# bristol_longshot.net
KiCad netlist of a schematic drawn in EAGLE
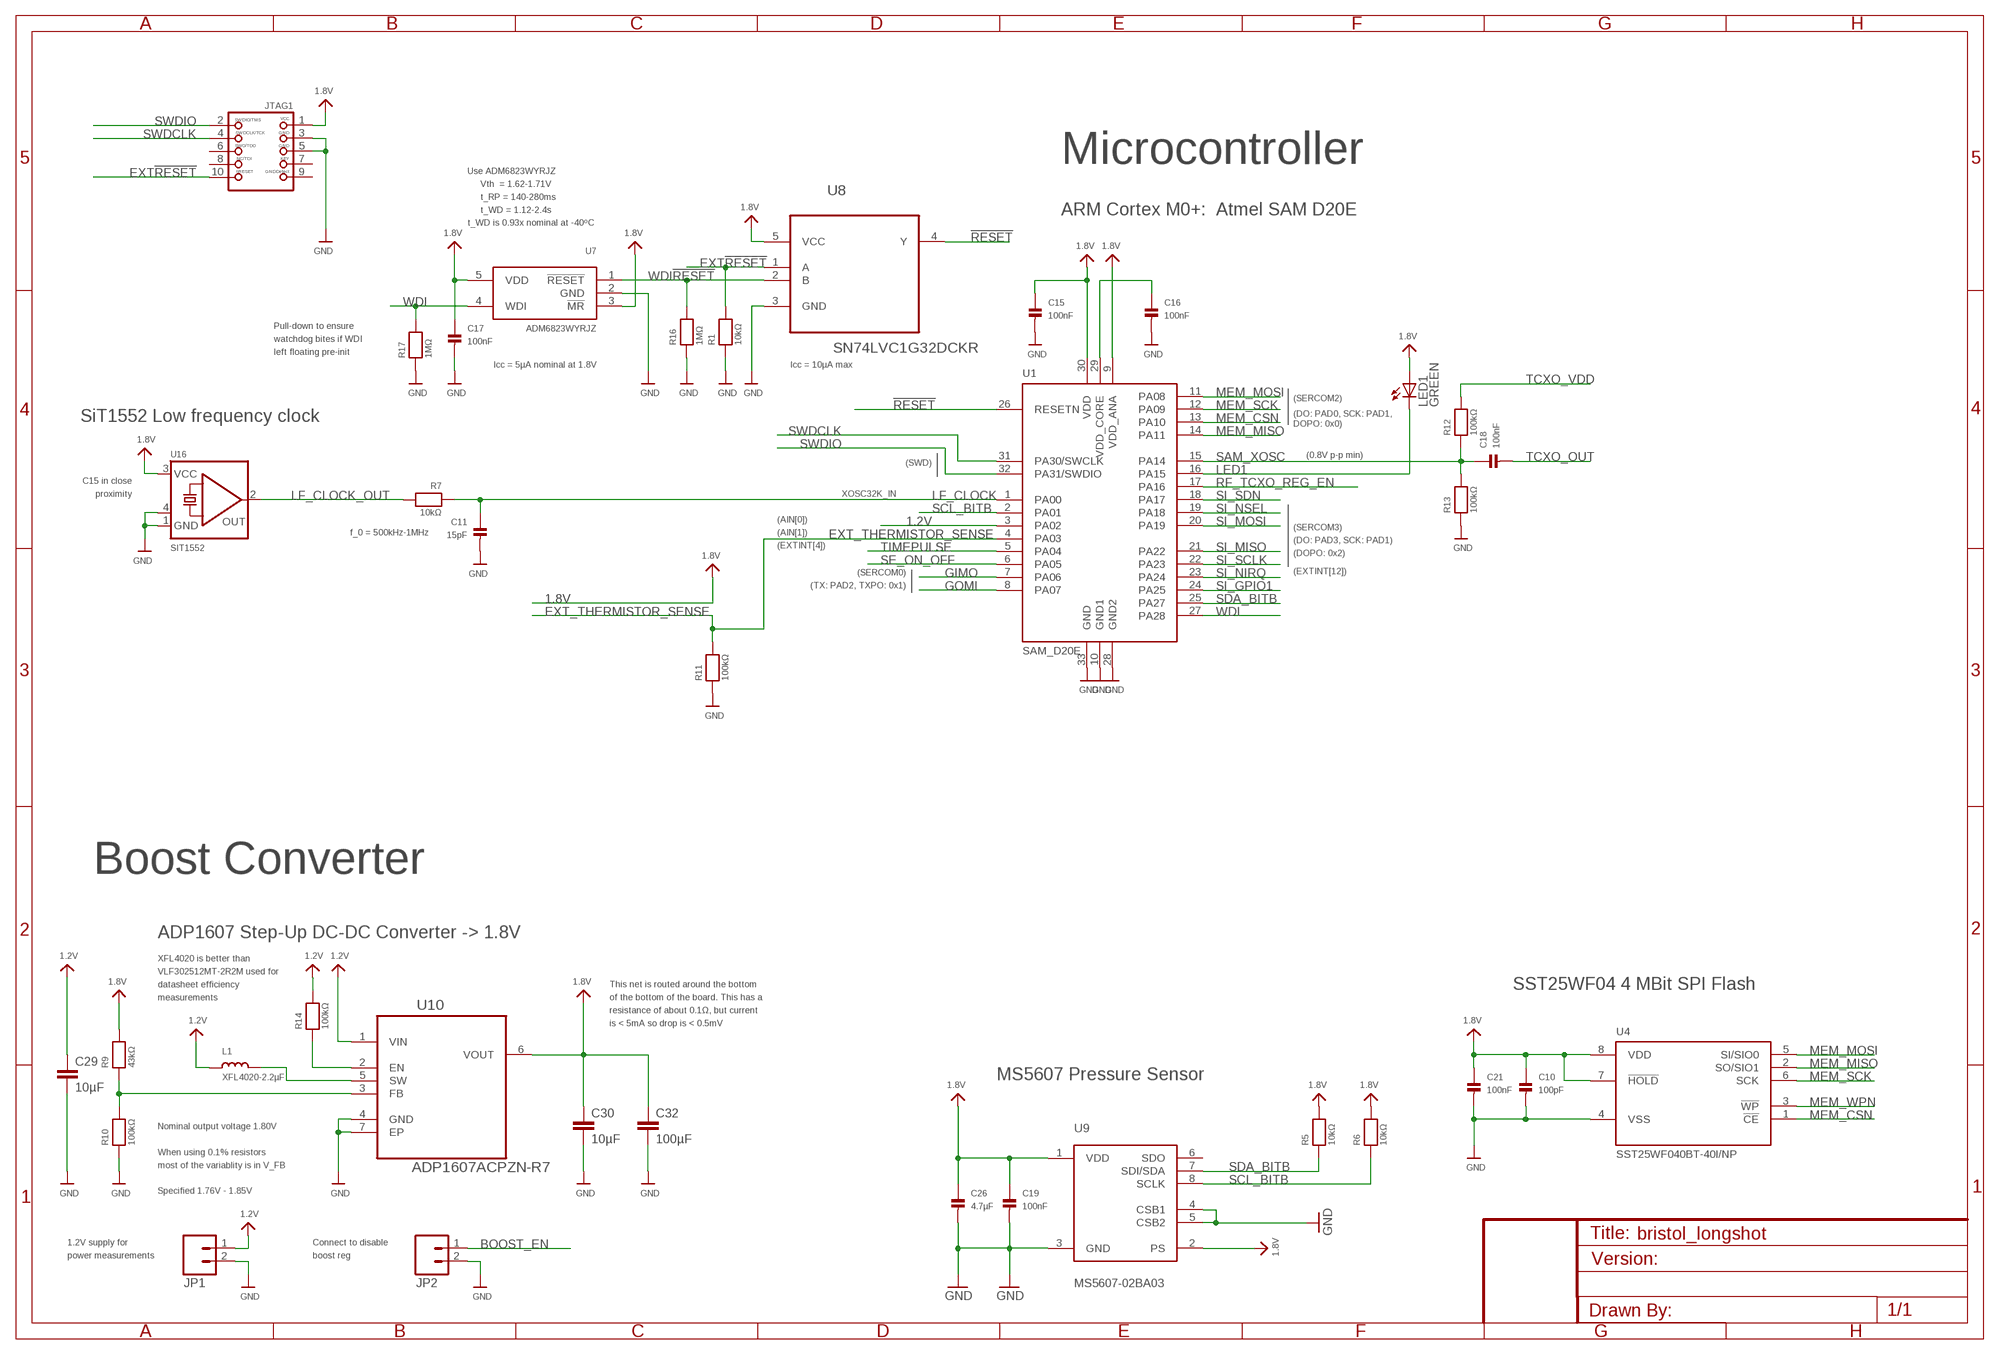
[diagram p0: schematic, sheet 1, part 1 of 2]
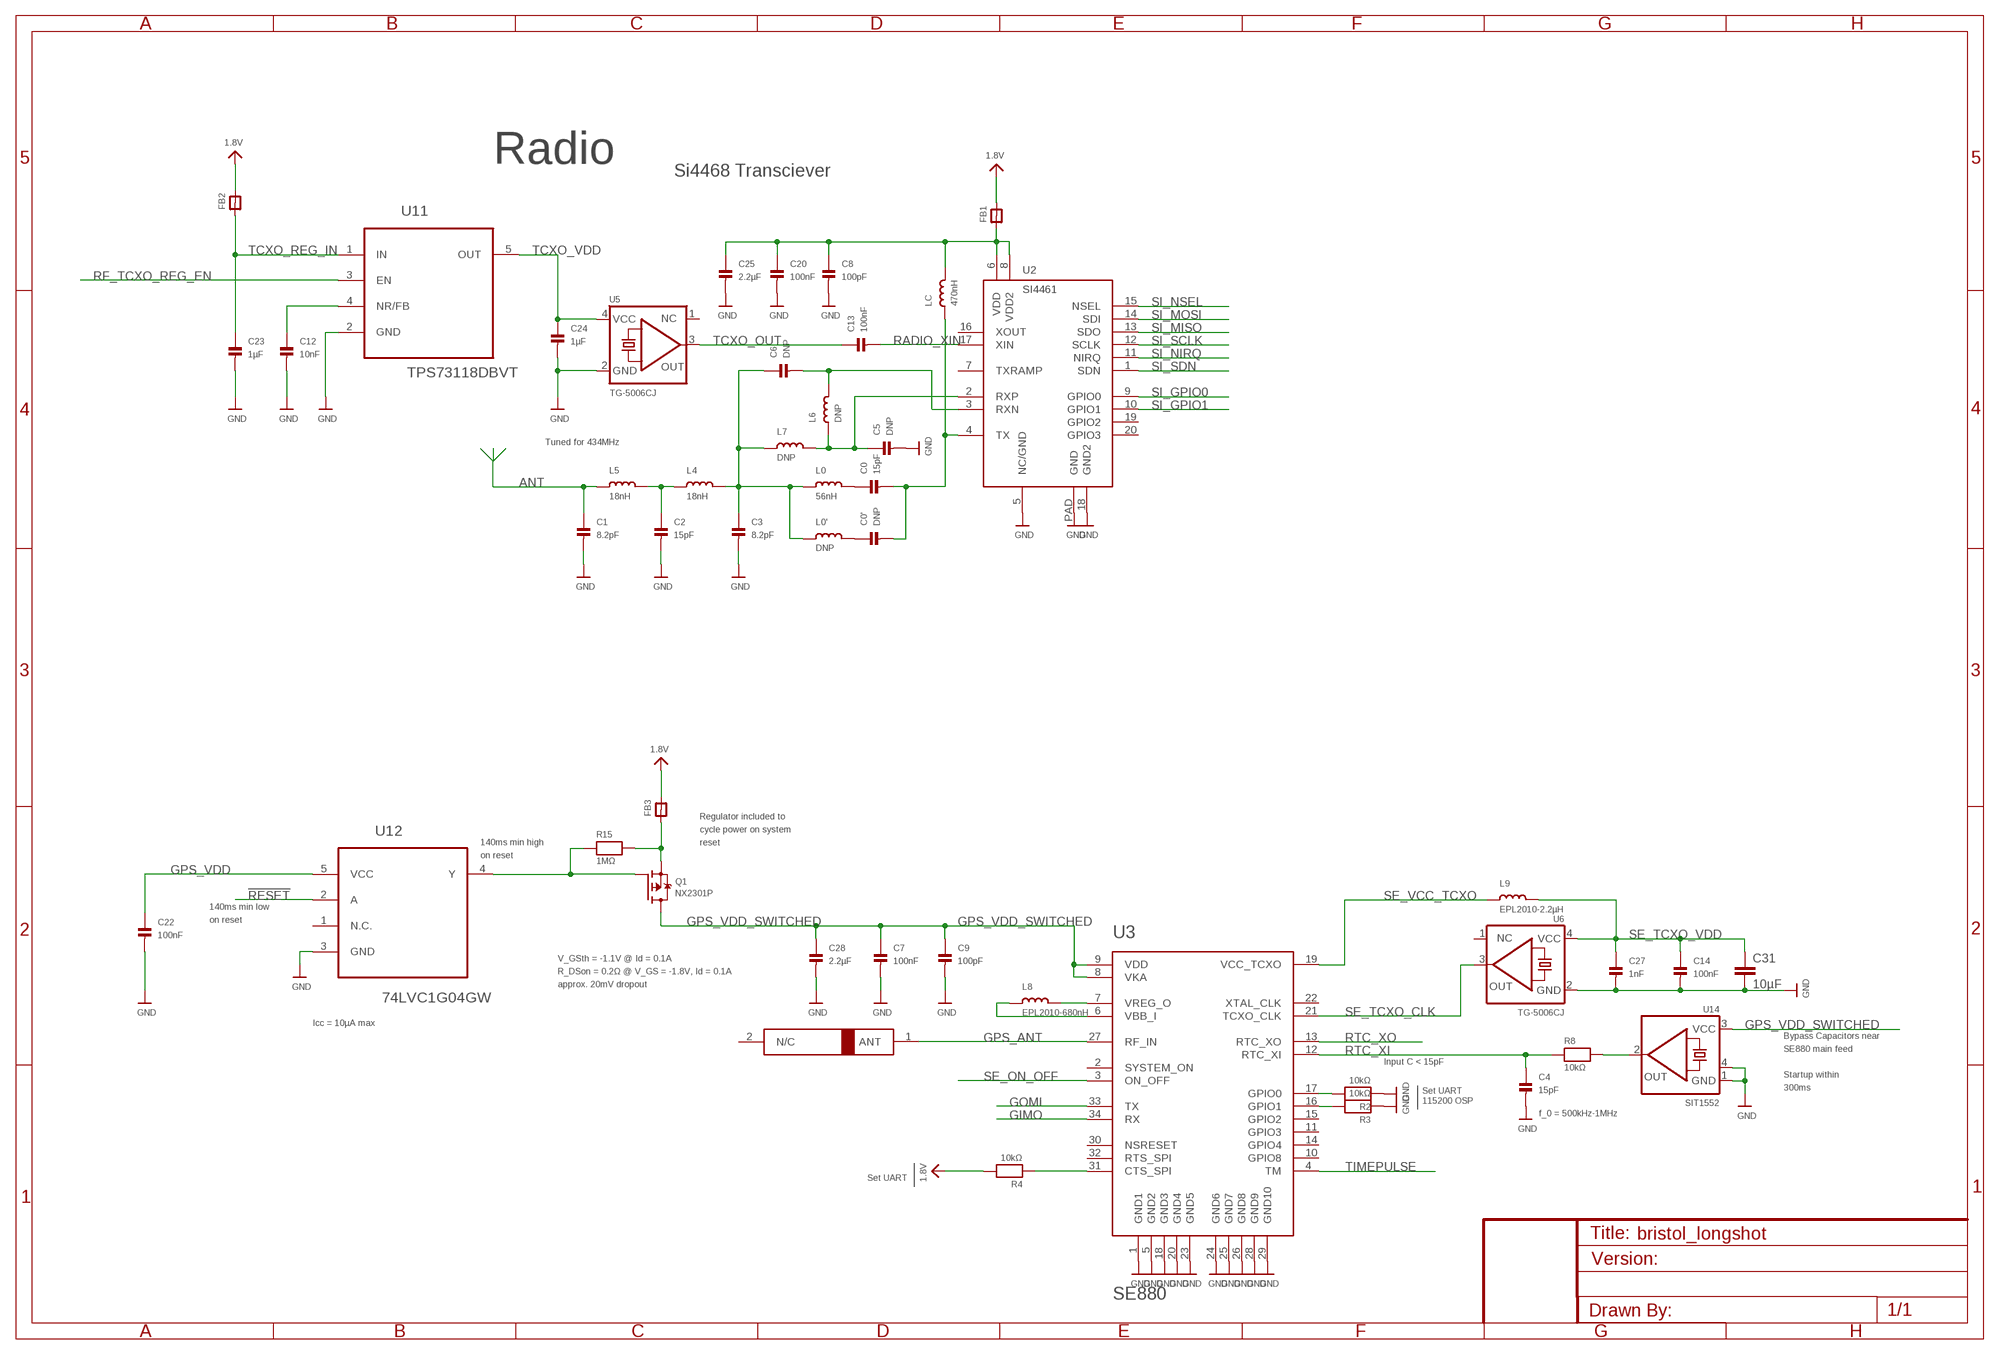
[diagram p1: schematic, sheet 1, part 2 of 2]

(export (version "E")
  (design (tool "Eeschema 10.0.6"))
  (components
    (comp (ref "A1")
      (value "1575AT43A40")
      (footprint "eagle-import:1575AT43A40")
      (libsource (lib "eagle-import") (part "1575AT43A40"))
    )
    (comp (ref "C0")
      (value "15pF")
      (footprint "eagle-import:_0402")
      (libsource (lib "eagle-import") (part "CAP_CERAMIC_0402"))
    )
    (comp (ref "C0'")
      (value "DNP")
      (footprint "eagle-import:_0402")
      (libsource (lib "eagle-import") (part "CAP_CERAMIC_0402"))
    )
    (comp (ref "C1")
      (value "8.2pF")
      (footprint "eagle-import:_0402")
      (libsource (lib "eagle-import") (part "CAP_CERAMIC_0402"))
    )
    (comp (ref "C2")
      (value "15pF")
      (footprint "eagle-import:_0402")
      (libsource (lib "eagle-import") (part "CAP_CERAMIC_0402"))
    )
    (comp (ref "C3")
      (value "8.2pF")
      (footprint "eagle-import:_0402")
      (libsource (lib "eagle-import") (part "CAP_CERAMIC_0402"))
    )
    (comp (ref "C4")
      (value "15pF")
      (footprint "eagle-import:_0402")
      (libsource (lib "eagle-import") (part "CAP_CERAMIC_0402"))
    )
    (comp (ref "C5")
      (value "DNP")
      (footprint "eagle-import:_0402")
      (libsource (lib "eagle-import") (part "CAP_CERAMIC_0402"))
    )
    (comp (ref "C6")
      (value "DNP")
      (footprint "eagle-import:_0402")
      (libsource (lib "eagle-import") (part "CAP_CERAMIC_0402"))
    )
    (comp (ref "C7")
      (value "100nF")
      (footprint "eagle-import:_0402")
      (libsource (lib "eagle-import") (part "CAP_CERAMIC_0402"))
    )
    (comp (ref "C8")
      (value "100pF")
      (footprint "eagle-import:_0402")
      (libsource (lib "eagle-import") (part "CAP_CERAMIC_0402"))
    )
    (comp (ref "C9")
      (value "100pF")
      (footprint "eagle-import:_0402")
      (libsource (lib "eagle-import") (part "CAP_CERAMIC_0402"))
    )
    (comp (ref "C10")
      (value "100pF")
      (footprint "eagle-import:_0402")
      (libsource (lib "eagle-import") (part "CAP_CERAMIC_0402"))
    )
    (comp (ref "C11")
      (value "15pF")
      (footprint "eagle-import:_0402")
      (libsource (lib "eagle-import") (part "CAP_CERAMIC_0402"))
    )
    (comp (ref "C12")
      (value "10nF")
      (footprint "eagle-import:_0402")
      (libsource (lib "eagle-import") (part "CAP_CERAMIC_0402"))
    )
    (comp (ref "C13")
      (value "100nF")
      (footprint "eagle-import:_0402")
      (libsource (lib "eagle-import") (part "CAP_CERAMIC_0402"))
    )
    (comp (ref "C14")
      (value "100nF")
      (footprint "eagle-import:_0402")
      (libsource (lib "eagle-import") (part "CAP_CERAMIC_0402"))
    )
    (comp (ref "C15")
      (value "100nF")
      (footprint "eagle-import:_0402")
      (libsource (lib "eagle-import") (part "CAP_CERAMIC_0402"))
    )
    (comp (ref "C16")
      (value "100nF")
      (footprint "eagle-import:_0402")
      (libsource (lib "eagle-import") (part "CAP_CERAMIC_0402"))
    )
    (comp (ref "C17")
      (value "100nF")
      (footprint "eagle-import:_0402")
      (libsource (lib "eagle-import") (part "CAP_CERAMIC_0402"))
    )
    (comp (ref "C18")
      (value "100nF")
      (footprint "eagle-import:_0402")
      (libsource (lib "eagle-import") (part "CAP_CERAMIC_0402"))
    )
    (comp (ref "C19")
      (value "100nF")
      (footprint "eagle-import:_0402")
      (libsource (lib "eagle-import") (part "CAP_CERAMIC_0402"))
    )
    (comp (ref "C20")
      (value "100nF")
      (footprint "eagle-import:_0402")
      (libsource (lib "eagle-import") (part "CAP_CERAMIC_0402"))
    )
    (comp (ref "C21")
      (value "100nF")
      (footprint "eagle-import:_0402")
      (libsource (lib "eagle-import") (part "CAP_CERAMIC_0402"))
    )
    (comp (ref "C22")
      (value "100nF")
      (footprint "eagle-import:_0402")
      (libsource (lib "eagle-import") (part "CAP_CERAMIC_0402"))
    )
    (comp (ref "C23")
      (value "1µF")
      (footprint "eagle-import:_0402")
      (libsource (lib "eagle-import") (part "CAP_CERAMIC_0402"))
    )
    (comp (ref "C24")
      (value "1µF")
      (footprint "eagle-import:_0402")
      (libsource (lib "eagle-import") (part "CAP_CERAMIC_0402"))
    )
    (comp (ref "C25")
      (value "2.2µF")
      (footprint "eagle-import:_0402")
      (libsource (lib "eagle-import") (part "CAP_CERAMIC_0402"))
    )
    (comp (ref "C26")
      (value "4.7µF")
      (footprint "eagle-import:_0402")
      (libsource (lib "eagle-import") (part "CAP_CERAMIC_0402"))
    )
    (comp (ref "C27")
      (value "1nF")
      (footprint "eagle-import:_0402")
      (libsource (lib "eagle-import") (part "CAP_CERAMIC_0402"))
    )
    (comp (ref "C28")
      (value "2.2µF")
      (footprint "eagle-import:_0402")
      (libsource (lib "eagle-import") (part "CAP_CERAMIC_0402"))
    )
    (comp (ref "C29")
      (value "10µF")
      (footprint "eagle-import:C0603K")
      (libsource (lib "eagle-import") (part "C-EUC0603K"))
    )
    (comp (ref "C30")
      (value "10µF")
      (footprint "eagle-import:C0603K")
      (libsource (lib "eagle-import") (part "C-EUC0603K"))
    )
    (comp (ref "C31")
      (value "10µF")
      (footprint "eagle-import:C0603K")
      (libsource (lib "eagle-import") (part "C-EUC0603K"))
    )
    (comp (ref "C32")
      (value "100µF")
      (footprint "eagle-import:C1206K")
      (libsource (lib "eagle-import") (part "C-EUC1206K"))
    )
    (comp (ref "FB1")
      (value "FERRITE_0402")
      (footprint "eagle-import:_0402@1")
      (libsource (lib "eagle-import") (part "FERRITE_0402"))
    )
    (comp (ref "FB2")
      (value "FERRITE_0402")
      (footprint "eagle-import:_0402@1")
      (libsource (lib "eagle-import") (part "FERRITE_0402"))
    )
    (comp (ref "FB3")
      (value "FERRITE_0402")
      (footprint "eagle-import:_0402@1")
      (libsource (lib "eagle-import") (part "FERRITE_0402"))
    )
    (comp (ref "JP1")
      (value "M02LOCK")
      (footprint "eagle-import:1X02_LOCK")
      (libsource (lib "eagle-import") (part "M02LOCK"))
    )
    (comp (ref "JP2")
      (value "M02LOCK")
      (footprint "eagle-import:1X02_LOCK")
      (libsource (lib "eagle-import") (part "M02LOCK"))
    )
    (comp (ref "JTAG1")
      (value "JTAG-CORTEXM3SMT")
      (footprint "eagle-import:2X05_1.27MM_SMT")
      (libsource (lib "eagle-import") (part "JTAG-CORTEXM3SMT"))
    )
    (comp (ref "L0")
      (value "56nH")
      (footprint "eagle-import:_0402")
      (libsource (lib "eagle-import") (part "INDUCTOR_0402"))
    )
    (comp (ref "L0'")
      (value "DNP")
      (footprint "eagle-import:_0402")
      (libsource (lib "eagle-import") (part "INDUCTOR_0402"))
    )
    (comp (ref "L1")
      (value "XFL4020-2.2µF")
      (footprint "eagle-import:XFL4020")
      (libsource (lib "eagle-import") (part "XFL4020"))
    )
    (comp (ref "L4")
      (value "18nH")
      (footprint "eagle-import:_0402")
      (libsource (lib "eagle-import") (part "INDUCTOR_0402"))
    )
    (comp (ref "L5")
      (value "18nH")
      (footprint "eagle-import:_0402")
      (libsource (lib "eagle-import") (part "INDUCTOR_0402"))
    )
    (comp (ref "L6")
      (value "DNP")
      (footprint "eagle-import:_0402")
      (libsource (lib "eagle-import") (part "INDUCTOR_0402"))
    )
    (comp (ref "L7")
      (value "DNP")
      (footprint "eagle-import:_0402")
      (libsource (lib "eagle-import") (part "INDUCTOR_0402"))
    )
    (comp (ref "L8")
      (value "EPL2010-680nH")
      (footprint "eagle-import:EPL2010")
      (libsource (lib "eagle-import") (part "EPL2010"))
    )
    (comp (ref "L9")
      (value "EPL2010-2.2µH")
      (footprint "eagle-import:EPL2010")
      (libsource (lib "eagle-import") (part "EPL2010"))
    )
    (comp (ref "LC")
      (value "470nH")
      (footprint "eagle-import:_0402")
      (libsource (lib "eagle-import") (part "INDUCTOR_0402"))
    )
    (comp (ref "LED1")
      (value "GREEN")
      (footprint "eagle-import:CHIPLED_0603")
      (libsource (lib "eagle-import") (part "LEDCHIPLED_0603"))
    )
    (comp (ref "Q1")
      (value "NX2301P")
      (footprint "eagle-import:SOT23")
      (libsource (lib "eagle-import") (part "NX2301P"))
    )
    (comp (ref "R1")
      (value "10kΩ")
      (footprint "eagle-import:_0402")
      (libsource (lib "eagle-import") (part "RESISTOR_0402"))
    )
    (comp (ref "R2")
      (value "10kΩ")
      (footprint "eagle-import:_0402")
      (libsource (lib "eagle-import") (part "RESISTOR_0402"))
    )
    (comp (ref "R3")
      (value "10kΩ")
      (footprint "eagle-import:_0402")
      (libsource (lib "eagle-import") (part "RESISTOR_0402"))
    )
    (comp (ref "R4")
      (value "10kΩ")
      (footprint "eagle-import:_0402")
      (libsource (lib "eagle-import") (part "RESISTOR_0402"))
    )
    (comp (ref "R5")
      (value "10kΩ")
      (footprint "eagle-import:_0402")
      (libsource (lib "eagle-import") (part "RESISTOR_0402"))
    )
    (comp (ref "R6")
      (value "10kΩ")
      (footprint "eagle-import:_0402")
      (libsource (lib "eagle-import") (part "RESISTOR_0402"))
    )
    (comp (ref "R7")
      (value "10kΩ")
      (footprint "eagle-import:_0402")
      (libsource (lib "eagle-import") (part "RESISTOR_0402"))
    )
    (comp (ref "R8")
      (value "10kΩ")
      (footprint "eagle-import:_0402")
      (libsource (lib "eagle-import") (part "RESISTOR_0402"))
    )
    (comp (ref "R9")
      (value "43kΩ")
      (footprint "eagle-import:_0402")
      (libsource (lib "eagle-import") (part "RESISTOR_0402"))
    )
    (comp (ref "R10")
      (value "100kΩ")
      (footprint "eagle-import:_0402")
      (libsource (lib "eagle-import") (part "RESISTOR_0402"))
    )
    (comp (ref "R11")
      (value "100kΩ")
      (footprint "eagle-import:_0402")
      (libsource (lib "eagle-import") (part "RESISTOR_0402"))
    )
    (comp (ref "R12")
      (value "100kΩ")
      (footprint "eagle-import:_0402")
      (libsource (lib "eagle-import") (part "RESISTOR_0402"))
    )
    (comp (ref "R13")
      (value "100kΩ")
      (footprint "eagle-import:_0402")
      (libsource (lib "eagle-import") (part "RESISTOR_0402"))
    )
    (comp (ref "R14")
      (value "100kΩ")
      (footprint "eagle-import:_0402")
      (libsource (lib "eagle-import") (part "RESISTOR_0402"))
    )
    (comp (ref "R15")
      (value "1MΩ")
      (footprint "eagle-import:_0402")
      (libsource (lib "eagle-import") (part "RESISTOR_0402"))
    )
    (comp (ref "R16")
      (value "1MΩ")
      (footprint "eagle-import:_0402")
      (libsource (lib "eagle-import") (part "RESISTOR_0402"))
    )
    (comp (ref "R17")
      (value "1MΩ")
      (footprint "eagle-import:_0402")
      (libsource (lib "eagle-import") (part "RESISTOR_0402"))
    )
    (comp (ref "U1")
      (value "SAM_D20E")
      (footprint "eagle-import:QFN32_5MM")
      (libsource (lib "eagle-import") (part "SAM_D20E"))
    )
    (comp (ref "U2")
      (value "SI4461")
      (footprint "eagle-import:QFN20")
      (libsource (lib "eagle-import") (part "SI4060"))
    )
    (comp (ref "U3")
      (value "SE880")
      (footprint "eagle-import:SE880")
      (libsource (lib "eagle-import") (part "SE880"))
    )
    (comp (ref "U4")
      (value "SST25WF040BT-40I/NP")
      (footprint "eagle-import:USON-8")
      (libsource (lib "eagle-import") (part "SST25WF040BT-40I/NP"))
    )
    (comp (ref "U5")
      (value "TG-5006CJ")
      (footprint "eagle-import:TC-5006CJ")
      (libsource (lib "eagle-import") (part "TG-5006CJ"))
    )
    (comp (ref "U6")
      (value "TG-5006CJ")
      (footprint "eagle-import:TC-5006CJ")
      (libsource (lib "eagle-import") (part "TG-5006CJ"))
    )
    (comp (ref "U7")
      (value "ADM6823WYRJZ")
      (footprint "eagle-import:SOT23-5")
      (libsource (lib "eagle-import") (part "TPS3123"))
    )
    (comp (ref "U8")
      (value "SN74LVC1G32DCKR")
      (footprint "eagle-import:SOT65P210X110-5N")
      (libsource (lib "eagle-import") (part "SN74LVC1G32DCKR"))
    )
    (comp (ref "U9")
      (value "MS5607-02BA03")
      (footprint "eagle-import:MS5607-02BA03")
      (libsource (lib "eagle-import") (part "MS5607-02BA03"))
    )
    (comp (ref "U10")
      (value "ADP1607ACPZN-R7")
      (footprint "eagle-import:DFN200X200X60-7N")
      (libsource (lib "eagle-import") (part "ADP1607ACPZN-R7"))
    )
    (comp (ref "U11")
      (value "TPS73118DBVT")
      (footprint "eagle-import:SOT95P280X145-5N")
      (libsource (lib "eagle-import") (part "TPS73118DBVT"))
    )
    (comp (ref "U12")
      (value "74LVC1G04GW")
      (footprint "eagle-import:SOT65P210X110-5N")
      (libsource (lib "eagle-import") (part "74LVC1G04GW"))
    )
    (comp (ref "U14")
      (value "SIT1552")
      (footprint "eagle-import:SIT1552")
      (libsource (lib "eagle-import") (part "SIT1552"))
    )
    (comp (ref "U16")
      (value "SIT1552")
      (footprint "eagle-import:SIT1552")
      (libsource (lib "eagle-import") (part "SIT1552"))
    )
  )
  (nets
    (net (code "1") (name "/ANT") (class "Default")
      (node (ref "C1") (pin "1") (pinfunction "P$1_1") (pintype "passive"))
      (node (ref "L5") (pin "1") (pinfunction "1_1") (pintype "passive"))
    )
    (net (code "2") (name "/BOOST_EN") (class "Default")
      (node (ref "JP2") (pin "1") (pinfunction "1_1") (pintype "passive"))
      (node (ref "R14") (pin "1") (pinfunction "1_1") (pintype "passive"))
      (node (ref "U10") (pin "2") (pinfunction "EN_2") (pintype "input"))
    )
    (net (code "3") (name "/EXT_THERMISTOR_SENSE") (class "Default")
      (node (ref "R11") (pin "2") (pinfunction "2_2") (pintype "passive"))
      (node (ref "U1") (pin "4") (pinfunction "PA03_4") (pintype "bidirectional"))
    )
    (net (code "4") (name "/EXT~{RESET}") (class "Default")
      (node (ref "JTAG1") (pin "10") (pinfunction "10_10") (pintype "passive"))
      (node (ref "R1") (pin "2") (pinfunction "2_2") (pintype "passive"))
      (node (ref "U8") (pin "1") (pinfunction "A_1") (pintype "input"))
    )
    (net (code "5") (name "/GIMO") (class "Default")
      (node (ref "U1") (pin "7") (pinfunction "PA06_7") (pintype "bidirectional"))
      (node (ref "U3") (pin "34") (pinfunction "RX_34") (pintype "bidirectional"))
    )
    (net (code "6") (name "/GOMI") (class "Default")
      (node (ref "U1") (pin "8") (pinfunction "PA07_8") (pintype "bidirectional"))
      (node (ref "U3") (pin "33") (pinfunction "TX_33") (pintype "bidirectional"))
    )
    (net (code "7") (name "/GPS_ANT") (class "Default")
      (node (ref "A1") (pin "1") (pinfunction "ANT_1") (pintype "bidirectional"))
      (node (ref "U3") (pin "27") (pinfunction "RF_IN_27") (pintype "bidirectional"))
    )
    (net (code "8") (name "/GPS_VDD") (class "Default")
      (node (ref "C22") (pin "1") (pinfunction "P$1_1") (pintype "passive"))
      (node (ref "FB3") (pin "1") (pinfunction "P$1_1") (pintype "passive"))
      (node (ref "Q1") (pin "2") (pinfunction "S_2") (pintype "passive"))
      (node (ref "R15") (pin "2") (pinfunction "2_2") (pintype "passive"))
      (node (ref "U12") (pin "5") (pinfunction "VCC_5") (pintype "power_in"))
    )
    (net (code "9") (name "/GPS_VDD_SWITCHED") (class "Default")
      (node (ref "C28") (pin "1") (pinfunction "P$1_1") (pintype "passive"))
      (node (ref "C7") (pin "1") (pinfunction "P$1_1") (pintype "passive"))
      (node (ref "C9") (pin "1") (pinfunction "P$1_1") (pintype "passive"))
      (node (ref "Q1") (pin "3") (pinfunction "D_3") (pintype "passive"))
      (node (ref "U14") (pin "3") (pinfunction "VCC_3") (pintype "power_in"))
      (node (ref "U3") (pin "8") (pinfunction "VKA_8") (pintype "bidirectional"))
      (node (ref "U3") (pin "9") (pinfunction "VDD_9") (pintype "bidirectional"))
    )
    (net (code "10") (name "/LED1") (class "Default")
      (node (ref "LED1") (pin "C") (pinfunction "C_C") (pintype "passive"))
      (node (ref "U1") (pin "16") (pinfunction "PA15_16") (pintype "bidirectional"))
    )
    (net (code "11") (name "/LF_CLOCK") (class "Default")
      (node (ref "C11") (pin "1") (pinfunction "P$1_1") (pintype "passive"))
      (node (ref "R7") (pin "1") (pinfunction "1_1") (pintype "passive"))
      (node (ref "U1") (pin "1") (pinfunction "PA00_1") (pintype "bidirectional"))
    )
    (net (code "12") (name "/LF_CLOCK_OUT") (class "Default")
      (node (ref "R7") (pin "2") (pinfunction "2_2") (pintype "passive"))
      (node (ref "U16") (pin "2") (pinfunction "OUT_2") (pintype "output"))
    )
    (net (code "13") (name "/MEM_CSN") (class "Default")
      (node (ref "U1") (pin "13") (pinfunction "PA10_13") (pintype "bidirectional"))
      (node (ref "U4") (pin "1") (pinfunction "~{CE}_1") (pintype "input"))
    )
    (net (code "14") (name "/MEM_MISO") (class "Default")
      (node (ref "U1") (pin "14") (pinfunction "PA11_14") (pintype "bidirectional"))
      (node (ref "U4") (pin "2") (pinfunction "SO/SIO1_2") (pintype "output"))
    )
    (net (code "15") (name "/MEM_MOSI") (class "Default")
      (node (ref "U1") (pin "11") (pinfunction "PA08_11") (pintype "bidirectional"))
      (node (ref "U4") (pin "5") (pinfunction "SI/SIO0_5") (pintype "bidirectional"))
    )
    (net (code "16") (name "/MEM_SCK") (class "Default")
      (node (ref "U1") (pin "12") (pinfunction "PA09_12") (pintype "bidirectional"))
      (node (ref "U4") (pin "6") (pinfunction "SCK_6") (pintype "input"))
    )
    (net (code "17") (name "/MEM_WPN") (class "Default")
      (node (ref "U4") (pin "3") (pinfunction "~{WP}_3") (pintype "output"))
    )
    (net (code "18") (name "/RADIO_XIN") (class "Default")
      (node (ref "C13") (pin "2") (pinfunction "P$2_2") (pintype "passive"))
      (node (ref "U2") (pin "17") (pinfunction "XIN_17") (pintype "input"))
    )
    (net (code "19") (name "/RF_TCXO_REG_EN") (class "Default")
      (node (ref "U1") (pin "17") (pinfunction "PA16_17") (pintype "bidirectional"))
      (node (ref "U11") (pin "3") (pinfunction "EN_3") (pintype "input"))
    )
    (net (code "20") (name "/RTC_XI") (class "Default")
      (node (ref "C4") (pin "1") (pinfunction "P$1_1") (pintype "passive"))
      (node (ref "R8") (pin "1") (pinfunction "1_1") (pintype "passive"))
      (node (ref "U3") (pin "12") (pinfunction "RTC_XI_12") (pintype "bidirectional"))
    )
    (net (code "21") (name "/RTC_XO") (class "Default")
      (node (ref "U3") (pin "13") (pinfunction "RTC_XO_13") (pintype "bidirectional"))
    )
    (net (code "22") (name "/SAM_XOSC") (class "Default")
      (node (ref "C18") (pin "1") (pinfunction "P$1_1") (pintype "passive"))
      (node (ref "R12") (pin "1") (pinfunction "1_1") (pintype "passive"))
      (node (ref "R13") (pin "2") (pinfunction "2_2") (pintype "passive"))
      (node (ref "U1") (pin "15") (pinfunction "PA14_15") (pintype "bidirectional"))
    )
    (net (code "23") (name "/SCL_BITB") (class "Default")
      (node (ref "R6") (pin "1") (pinfunction "1_1") (pintype "passive"))
      (node (ref "U1") (pin "2") (pinfunction "PA01_2") (pintype "bidirectional"))
      (node (ref "U9") (pin "8") (pinfunction "SCLK_8") (pintype "bidirectional"))
    )
    (net (code "24") (name "/SDA_BITB") (class "Default")
      (node (ref "R5") (pin "1") (pinfunction "1_1") (pintype "passive"))
      (node (ref "U1") (pin "25") (pinfunction "PA27_25") (pintype "bidirectional"))
      (node (ref "U9") (pin "7") (pinfunction "SDI/SDA_7") (pintype "bidirectional"))
    )
    (net (code "25") (name "/SE_ON_OFF") (class "Default")
      (node (ref "U1") (pin "6") (pinfunction "PA05_6") (pintype "bidirectional"))
      (node (ref "U3") (pin "3") (pinfunction "ON_OFF_3") (pintype "bidirectional"))
    )
    (net (code "26") (name "/SE_TCXO_CLK") (class "Default")
      (node (ref "U3") (pin "21") (pinfunction "TCXO_CLK_21") (pintype "bidirectional"))
      (node (ref "U6") (pin "3") (pinfunction "OUT_3") (pintype "output"))
    )
    (net (code "27") (name "/SE_TCXO_VDD") (class "Default")
      (node (ref "C14") (pin "1") (pinfunction "P$1_1") (pintype "passive"))
      (node (ref "C27") (pin "1") (pinfunction "P$1_1") (pintype "passive"))
      (node (ref "C31") (pin "1") (pinfunction "1_1") (pintype "passive"))
      (node (ref "L9") (pin "2") (pinfunction "2_2") (pintype "passive"))
      (node (ref "U6") (pin "4") (pinfunction "VCC_4") (pintype "power_in"))
    )
    (net (code "28") (name "/SE_VCC_TCXO") (class "Default")
      (node (ref "L9") (pin "1") (pinfunction "1_1") (pintype "passive"))
      (node (ref "U3") (pin "19") (pinfunction "VCC_TCXO_19") (pintype "bidirectional"))
    )
    (net (code "29") (name "/SI_GPIO0") (class "Default")
      (node (ref "U2") (pin "9") (pinfunction "GPIO0_9") (pintype "bidirectional"))
    )
    (net (code "30") (name "/SI_GPIO1") (class "Default")
      (node (ref "U1") (pin "24") (pinfunction "PA25_24") (pintype "bidirectional"))
      (node (ref "U2") (pin "10") (pinfunction "GPIO1_10") (pintype "bidirectional"))
    )
    (net (code "31") (name "/SI_MISO") (class "Default")
      (node (ref "U1") (pin "21") (pinfunction "PA22_21") (pintype "bidirectional"))
      (node (ref "U2") (pin "13") (pinfunction "SDO_13") (pintype "output"))
    )
    (net (code "32") (name "/SI_MOSI") (class "Default")
      (node (ref "U1") (pin "20") (pinfunction "PA19_20") (pintype "bidirectional"))
      (node (ref "U2") (pin "14") (pinfunction "SDI_14") (pintype "bidirectional"))
    )
    (net (code "33") (name "/SI_NIRQ") (class "Default")
      (node (ref "U1") (pin "23") (pinfunction "PA24_23") (pintype "bidirectional"))
      (node (ref "U2") (pin "11") (pinfunction "NIRQ_11") (pintype "output"))
    )
    (net (code "34") (name "/SI_NSEL") (class "Default")
      (node (ref "U1") (pin "19") (pinfunction "PA18_19") (pintype "bidirectional"))
      (node (ref "U2") (pin "15") (pinfunction "NSEL_15") (pintype "input"))
    )
    (net (code "35") (name "/SI_SCLK") (class "Default")
      (node (ref "U1") (pin "22") (pinfunction "PA23_22") (pintype "bidirectional"))
      (node (ref "U2") (pin "12") (pinfunction "SCLK_12") (pintype "input"))
    )
    (net (code "36") (name "/SI_SDN") (class "Default")
      (node (ref "U1") (pin "18") (pinfunction "PA17_18") (pintype "bidirectional"))
      (node (ref "U2") (pin "1") (pinfunction "SDN_1") (pintype "input"))
    )
    (net (code "37") (name "/SWDCLK") (class "Default")
      (node (ref "JTAG1") (pin "4") (pinfunction "4_4") (pintype "passive"))
      (node (ref "U1") (pin "31") (pinfunction "PA30/SWCLK_31") (pintype "bidirectional"))
    )
    (net (code "38") (name "/SWDIO") (class "Default")
      (node (ref "JTAG1") (pin "2") (pinfunction "2_2") (pintype "passive"))
      (node (ref "U1") (pin "32") (pinfunction "PA31/SWDIO_32") (pintype "bidirectional"))
    )
    (net (code "39") (name "/TCXO_OUT") (class "Default")
      (node (ref "C13") (pin "1") (pinfunction "P$1_1") (pintype "passive"))
      (node (ref "C18") (pin "2") (pinfunction "P$2_2") (pintype "passive"))
      (node (ref "U5") (pin "3") (pinfunction "OUT_3") (pintype "output"))
    )
    (net (code "40") (name "/TCXO_REG_IN") (class "Default")
      (node (ref "C23") (pin "1") (pinfunction "P$1_1") (pintype "passive"))
      (node (ref "FB2") (pin "1") (pinfunction "P$1_1") (pintype "passive"))
      (node (ref "U11") (pin "1") (pinfunction "IN_1") (pintype "power_in"))
    )
    (net (code "41") (name "/TCXO_VDD") (class "Default")
      (node (ref "C24") (pin "1") (pinfunction "P$1_1") (pintype "passive"))
      (node (ref "R12") (pin "2") (pinfunction "2_2") (pintype "passive"))
      (node (ref "U11") (pin "5") (pinfunction "OUT_5") (pintype "output"))
      (node (ref "U5") (pin "4") (pinfunction "VCC_4") (pintype "power_in"))
    )
    (net (code "42") (name "/TIMEPULSE") (class "Default")
      (node (ref "U1") (pin "5") (pinfunction "PA04_5") (pintype "bidirectional"))
      (node (ref "U3") (pin "4") (pinfunction "TM_4") (pintype "bidirectional"))
    )
    (net (code "43") (name "/WDI") (class "Default")
      (node (ref "R17") (pin "2") (pinfunction "2_2") (pintype "passive"))
      (node (ref "U1") (pin "27") (pinfunction "PA28_27") (pintype "bidirectional"))
      (node (ref "U7") (pin "4") (pinfunction "WDI_4") (pintype "bidirectional"))
    )
    (net (code "44") (name "/WDI~{RESET}") (class "Default")
      (node (ref "R16") (pin "2") (pinfunction "2_2") (pintype "passive"))
      (node (ref "U7") (pin "1") (pinfunction "~{RESET}_1") (pintype "bidirectional"))
      (node (ref "U8") (pin "2") (pinfunction "B_2") (pintype "input"))
    )
    (net (code "45") (name "/~{RESET}") (class "Default")
      (node (ref "U1") (pin "26") (pinfunction "RESETN_26") (pintype "input"))
      (node (ref "U12") (pin "2") (pinfunction "A_2") (pintype "input"))
      (node (ref "U8") (pin "4") (pinfunction "Y_4") (pintype "output"))
    )
    (net (code "46") (name "1.2V") (class "Default")
      (node (ref "C29") (pin "1") (pinfunction "1_1") (pintype "passive"))
      (node (ref "JP1") (pin "1") (pinfunction "1_1") (pintype "passive"))
      (node (ref "L1") (pin "1") (pinfunction "1_1") (pintype "passive"))
      (node (ref "R14") (pin "2") (pinfunction "2_2") (pintype "passive"))
      (node (ref "U1") (pin "3") (pinfunction "PA02_3") (pintype "bidirectional"))
      (node (ref "U10") (pin "1") (pinfunction "VIN_1") (pintype "power_in"))
    )
    (net (code "47") (name "1.8V") (class "Default")
      (node (ref "C10") (pin "1") (pinfunction "P$1_1") (pintype "passive"))
      (node (ref "C15") (pin "1") (pinfunction "P$1_1") (pintype "passive"))
      (node (ref "C17") (pin "1") (pinfunction "P$1_1") (pintype "passive"))
      (node (ref "C19") (pin "1") (pinfunction "P$1_1") (pintype "passive"))
      (node (ref "C21") (pin "1") (pinfunction "P$1_1") (pintype "passive"))
      (node (ref "C26") (pin "1") (pinfunction "P$1_1") (pintype "passive"))
      (node (ref "C30") (pin "1") (pinfunction "1_1") (pintype "passive"))
      (node (ref "C32") (pin "1") (pinfunction "1_1") (pintype "passive"))
      (node (ref "FB1") (pin "2") (pinfunction "P$2_2") (pintype "passive"))
      (node (ref "FB2") (pin "2") (pinfunction "P$2_2") (pintype "passive"))
      (node (ref "FB3") (pin "2") (pinfunction "P$2_2") (pintype "passive"))
      (node (ref "JTAG1") (pin "1") (pinfunction "1_1") (pintype "passive"))
      (node (ref "LED1") (pin "A") (pinfunction "A_A") (pintype "passive"))
      (node (ref "R4") (pin "2") (pinfunction "2_2") (pintype "passive"))
      (node (ref "R5") (pin "2") (pinfunction "2_2") (pintype "passive"))
      (node (ref "R6") (pin "2") (pinfunction "2_2") (pintype "passive"))
      (node (ref "R9") (pin "2") (pinfunction "2_2") (pintype "passive"))
      (node (ref "U1") (pin "30") (pinfunction "VDD_30") (pintype "power_in"))
      (node (ref "U1") (pin "9") (pinfunction "VDD_ANA_9") (pintype "power_in"))
      (node (ref "U10") (pin "6") (pinfunction "VOUT_6") (pintype "output"))
      (node (ref "U16") (pin "3") (pinfunction "VCC_3") (pintype "power_in"))
      (node (ref "U4") (pin "7") (pinfunction "~{HOLD}_7") (pintype "output"))
      (node (ref "U4") (pin "8") (pinfunction "VDD_8") (pintype "power_in"))
      (node (ref "U7") (pin "3") (pinfunction "~{MR}_3") (pintype "bidirectional"))
      (node (ref "U7") (pin "5") (pinfunction "VDD_5") (pintype "bidirectional"))
      (node (ref "U8") (pin "5") (pinfunction "VCC_5") (pintype "power_in"))
      (node (ref "U9") (pin "1") (pinfunction "VDD_1") (pintype "bidirectional"))
      (node (ref "U9") (pin "2") (pinfunction "PS_2") (pintype "bidirectional"))
    )
    (net (code "48") (name "GND") (class "Default")
      (node (ref "C1") (pin "2") (pinfunction "P$2_2") (pintype "passive"))
      (node (ref "C10") (pin "2") (pinfunction "P$2_2") (pintype "passive"))
      (node (ref "C11") (pin "2") (pinfunction "P$2_2") (pintype "passive"))
      (node (ref "C12") (pin "2") (pinfunction "P$2_2") (pintype "passive"))
      (node (ref "C14") (pin "2") (pinfunction "P$2_2") (pintype "passive"))
      (node (ref "C15") (pin "2") (pinfunction "P$2_2") (pintype "passive"))
      (node (ref "C16") (pin "2") (pinfunction "P$2_2") (pintype "passive"))
      (node (ref "C17") (pin "2") (pinfunction "P$2_2") (pintype "passive"))
      (node (ref "C19") (pin "2") (pinfunction "P$2_2") (pintype "passive"))
      (node (ref "C2") (pin "2") (pinfunction "P$2_2") (pintype "passive"))
      (node (ref "C20") (pin "2") (pinfunction "P$2_2") (pintype "passive"))
      (node (ref "C21") (pin "2") (pinfunction "P$2_2") (pintype "passive"))
      (node (ref "C22") (pin "2") (pinfunction "P$2_2") (pintype "passive"))
      (node (ref "C23") (pin "2") (pinfunction "P$2_2") (pintype "passive"))
      (node (ref "C24") (pin "2") (pinfunction "P$2_2") (pintype "passive"))
      (node (ref "C25") (pin "2") (pinfunction "P$2_2") (pintype "passive"))
      (node (ref "C26") (pin "2") (pinfunction "P$2_2") (pintype "passive"))
      (node (ref "C27") (pin "2") (pinfunction "P$2_2") (pintype "passive"))
      (node (ref "C28") (pin "2") (pinfunction "P$2_2") (pintype "passive"))
      (node (ref "C29") (pin "2") (pinfunction "2_2") (pintype "passive"))
      (node (ref "C3") (pin "2") (pinfunction "P$2_2") (pintype "passive"))
      (node (ref "C30") (pin "2") (pinfunction "2_2") (pintype "passive"))
      (node (ref "C31") (pin "2") (pinfunction "2_2") (pintype "passive"))
      (node (ref "C32") (pin "2") (pinfunction "2_2") (pintype "passive"))
      (node (ref "C4") (pin "2") (pinfunction "P$2_2") (pintype "passive"))
      (node (ref "C5") (pin "2") (pinfunction "P$2_2") (pintype "passive"))
      (node (ref "C7") (pin "2") (pinfunction "P$2_2") (pintype "passive"))
      (node (ref "C8") (pin "2") (pinfunction "P$2_2") (pintype "passive"))
      (node (ref "C9") (pin "2") (pinfunction "P$2_2") (pintype "passive"))
      (node (ref "JP1") (pin "2") (pinfunction "2_2") (pintype "passive"))
      (node (ref "JP2") (pin "2") (pinfunction "2_2") (pintype "passive"))
      (node (ref "JTAG1") (pin "3") (pinfunction "3_3") (pintype "passive"))
      (node (ref "JTAG1") (pin "5") (pinfunction "5_5") (pintype "passive"))
      (node (ref "R1") (pin "1") (pinfunction "1_1") (pintype "passive"))
      (node (ref "R10") (pin "1") (pinfunction "1_1") (pintype "passive"))
      (node (ref "R11") (pin "1") (pinfunction "1_1") (pintype "passive"))
      (node (ref "R13") (pin "1") (pinfunction "1_1") (pintype "passive"))
      (node (ref "R16") (pin "1") (pinfunction "1_1") (pintype "passive"))
      (node (ref "R17") (pin "1") (pinfunction "1_1") (pintype "passive"))
      (node (ref "R2") (pin "1") (pinfunction "1_1") (pintype "passive"))
      (node (ref "R3") (pin "1") (pinfunction "1_1") (pintype "passive"))
      (node (ref "U1") (pin "10") (pinfunction "GND1_10") (pintype "power_in"))
      (node (ref "U1") (pin "28") (pinfunction "GND2_28") (pintype "power_in"))
      (node (ref "U1") (pin "33") (pinfunction "GND_33") (pintype "power_in"))
      (node (ref "U10") (pin "4") (pinfunction "GND_4") (pintype "power_in"))
      (node (ref "U10") (pin "7") (pinfunction "EP_7") (pintype "passive"))
      (node (ref "U11") (pin "2") (pinfunction "GND_2") (pintype "passive"))
      (node (ref "U12") (pin "3") (pinfunction "GND_3") (pintype "passive"))
      (node (ref "U14") (pin "1") (pinfunction "GND_1") (pintype "power_in"))
      (node (ref "U14") (pin "4") (pinfunction "GND1_4") (pintype "power_in"))
      (node (ref "U16") (pin "1") (pinfunction "GND_1") (pintype "power_in"))
      (node (ref "U16") (pin "4") (pinfunction "GND1_4") (pintype "power_in"))
      (node (ref "U2") (pin "18") (pinfunction "GND2_18") (pintype "power_in"))
      (node (ref "U2") (pin "5") (pinfunction "NC/GND_5") (pintype "bidirectional"))
      (node (ref "U2") (pin "PAD") (pinfunction "GND_PAD") (pintype "power_in"))
      (node (ref "U3") (pin "1") (pinfunction "GND1_1") (pintype "bidirectional"))
      (node (ref "U3") (pin "18") (pinfunction "GND3_18") (pintype "bidirectional"))
      (node (ref "U3") (pin "20") (pinfunction "GND4_20") (pintype "bidirectional"))
      (node (ref "U3") (pin "23") (pinfunction "GND5_23") (pintype "bidirectional"))
      (node (ref "U3") (pin "24") (pinfunction "GND6_24") (pintype "bidirectional"))
      (node (ref "U3") (pin "25") (pinfunction "GND7_25") (pintype "bidirectional"))
      (node (ref "U3") (pin "26") (pinfunction "GND8_26") (pintype "bidirectional"))
      (node (ref "U3") (pin "28") (pinfunction "GND9_28") (pintype "bidirectional"))
      (node (ref "U3") (pin "29") (pinfunction "GND10_29") (pintype "bidirectional"))
      (node (ref "U3") (pin "5") (pinfunction "GND2_5") (pintype "bidirectional"))
      (node (ref "U4") (pin "4") (pinfunction "VSS_4") (pintype "power_in"))
      (node (ref "U5") (pin "2") (pinfunction "GND_2") (pintype "power_in"))
      (node (ref "U6") (pin "2") (pinfunction "GND_2") (pintype "power_in"))
      (node (ref "U7") (pin "2") (pinfunction "GND_2") (pintype "bidirectional"))
      (node (ref "U8") (pin "3") (pinfunction "GND_3") (pintype "passive"))
      (node (ref "U9") (pin "3") (pinfunction "GND_3") (pintype "bidirectional"))
      (node (ref "U9") (pin "4") (pinfunction "CSB1_4") (pintype "bidirectional"))
      (node (ref "U9") (pin "5") (pinfunction "CSB2_5") (pintype "bidirectional"))
    )
    (net (code "49") (name "Net-(C0'-P$1)") (class "Default")
      (node (ref "C0'") (pin "1") (pinfunction "P$1_1") (pintype "passive"))
      (node (ref "L0'") (pin "2") (pinfunction "2_2") (pintype "passive"))
    )
    (net (code "50") (name "Net-(C0'-P$2)") (class "Default")
      (node (ref "C0") (pin "2") (pinfunction "P$2_2") (pintype "passive"))
      (node (ref "C0'") (pin "2") (pinfunction "P$2_2") (pintype "passive"))
      (node (ref "LC") (pin "1") (pinfunction "1_1") (pintype "passive"))
      (node (ref "U2") (pin "4") (pinfunction "TX_4") (pintype "output"))
    )
    (net (code "51") (name "Net-(C0-P$1)") (class "Default")
      (node (ref "C0") (pin "1") (pinfunction "P$1_1") (pintype "passive"))
      (node (ref "L0") (pin "2") (pinfunction "2_2") (pintype "passive"))
    )
    (net (code "52") (name "Net-(C2-P$1)") (class "Default")
      (node (ref "C2") (pin "1") (pinfunction "P$1_1") (pintype "passive"))
      (node (ref "L4") (pin "1") (pinfunction "1_1") (pintype "passive"))
      (node (ref "L5") (pin "2") (pinfunction "2_2") (pintype "passive"))
    )
    (net (code "53") (name "Net-(C3-P$1)") (class "Default")
      (node (ref "C3") (pin "1") (pinfunction "P$1_1") (pintype "passive"))
      (node (ref "C6") (pin "1") (pinfunction "P$1_1") (pintype "passive"))
      (node (ref "L0") (pin "1") (pinfunction "1_1") (pintype "passive"))
      (node (ref "L0'") (pin "1") (pinfunction "1_1") (pintype "passive"))
      (node (ref "L4") (pin "2") (pinfunction "2_2") (pintype "passive"))
      (node (ref "L7") (pin "1") (pinfunction "1_1") (pintype "passive"))
    )
    (net (code "54") (name "Net-(C5-P$1)") (class "Default")
      (node (ref "C5") (pin "1") (pinfunction "P$1_1") (pintype "passive"))
      (node (ref "L6") (pin "1") (pinfunction "1_1") (pintype "passive"))
      (node (ref "L7") (pin "2") (pinfunction "2_2") (pintype "passive"))
      (node (ref "U2") (pin "2") (pinfunction "RXP_2") (pintype "input"))
    )
    (net (code "55") (name "Net-(C6-P$2)") (class "Default")
      (node (ref "C6") (pin "2") (pinfunction "P$2_2") (pintype "passive"))
      (node (ref "L6") (pin "2") (pinfunction "2_2") (pintype "passive"))
      (node (ref "U2") (pin "3") (pinfunction "RXN_3") (pintype "input"))
    )
    (net (code "56") (name "Net-(C12-P$1)") (class "Default")
      (node (ref "C12") (pin "1") (pinfunction "P$1_1") (pintype "passive"))
      (node (ref "U11") (pin "4") (pinfunction "NR/FB_4") (pintype "passive"))
    )
    (net (code "57") (name "Net-(C16-P$1)") (class "Default")
      (node (ref "C16") (pin "1") (pinfunction "P$1_1") (pintype "passive"))
      (node (ref "U1") (pin "29") (pinfunction "VDD_CORE_29") (pintype "power_in"))
    )
    (net (code "58") (name "Net-(C20-P$1)") (class "Default")
      (node (ref "C20") (pin "1") (pinfunction "P$1_1") (pintype "passive"))
      (node (ref "C25") (pin "1") (pinfunction "P$1_1") (pintype "passive"))
      (node (ref "C8") (pin "1") (pinfunction "P$1_1") (pintype "passive"))
      (node (ref "FB1") (pin "1") (pinfunction "P$1_1") (pintype "passive"))
      (node (ref "LC") (pin "2") (pinfunction "2_2") (pintype "passive"))
      (node (ref "U2") (pin "6") (pinfunction "VDD_6") (pintype "power_in"))
      (node (ref "U2") (pin "8") (pinfunction "VDD2_8") (pintype "power_in"))
    )
    (net (code "59") (name "Net-(Q1-G)") (class "Default")
      (node (ref "Q1") (pin "1") (pinfunction "G_1") (pintype "passive"))
      (node (ref "R15") (pin "1") (pinfunction "1_1") (pintype "passive"))
      (node (ref "U12") (pin "4") (pinfunction "Y_4") (pintype "output"))
    )
    (net (code "60") (name "Net-(U3-CTS_SPI)") (class "Default")
      (node (ref "R4") (pin "1") (pinfunction "1_1") (pintype "passive"))
      (node (ref "U3") (pin "31") (pinfunction "CTS_SPI_31") (pintype "bidirectional"))
    )
    (net (code "61") (name "Net-(U3-GPIO0)") (class "Default")
      (node (ref "R2") (pin "2") (pinfunction "2_2") (pintype "passive"))
      (node (ref "U3") (pin "17") (pinfunction "GPIO0_17") (pintype "bidirectional"))
    )
    (net (code "62") (name "Net-(U3-GPIO1)") (class "Default")
      (node (ref "R3") (pin "2") (pinfunction "2_2") (pintype "passive"))
      (node (ref "U3") (pin "16") (pinfunction "GPIO1_16") (pintype "bidirectional"))
    )
    (net (code "63") (name "Net-(U3-VBB_I)") (class "Default")
      (node (ref "L8") (pin "1") (pinfunction "1_1") (pintype "passive"))
      (node (ref "U3") (pin "6") (pinfunction "VBB_I_6") (pintype "bidirectional"))
    )
    (net (code "64") (name "Net-(U3-VREG_O)") (class "Default")
      (node (ref "L8") (pin "2") (pinfunction "2_2") (pintype "passive"))
      (node (ref "U3") (pin "7") (pinfunction "VREG_O_7") (pintype "bidirectional"))
    )
    (net (code "65") (name "Net-(U10-FB)") (class "Default")
      (node (ref "R10") (pin "2") (pinfunction "2_2") (pintype "passive"))
      (node (ref "R9") (pin "1") (pinfunction "1_1") (pintype "passive"))
      (node (ref "U10") (pin "3") (pinfunction "FB_3") (pintype "passive"))
    )
    (net (code "66") (name "Net-(U10-SW)") (class "Default")
      (node (ref "L1") (pin "2") (pinfunction "2_2") (pintype "passive"))
      (node (ref "U10") (pin "5") (pinfunction "SW_5") (pintype "passive"))
    )
    (net (code "67") (name "Net-(U14-OUT)") (class "Default")
      (node (ref "R8") (pin "2") (pinfunction "2_2") (pintype "passive"))
      (node (ref "U14") (pin "2") (pinfunction "OUT_2") (pintype "output"))
    )
    (net (code "68") (name "unconnected-(A1-N{slash}C-Pad2)") (class "Default")
      (node (ref "A1") (pin "2") (pinfunction "N/C_2") (pintype "input"))
    )
    (net (code "69") (name "unconnected-(JTAG1-Pad6)") (class "Default")
      (node (ref "JTAG1") (pin "6") (pinfunction "6_6") (pintype "passive"))
    )
    (net (code "70") (name "unconnected-(JTAG1-Pad7)") (class "Default")
      (node (ref "JTAG1") (pin "7") (pinfunction "7_7") (pintype "passive"))
    )
    (net (code "71") (name "unconnected-(JTAG1-Pad8)") (class "Default")
      (node (ref "JTAG1") (pin "8") (pinfunction "8_8") (pintype "passive"))
    )
    (net (code "72") (name "unconnected-(JTAG1-Pad9)") (class "Default")
      (node (ref "JTAG1") (pin "9") (pinfunction "9_9") (pintype "passive"))
    )
    (net (code "73") (name "unconnected-(U2-GPIO2-Pad19)") (class "Default")
      (node (ref "U2") (pin "19") (pinfunction "GPIO2_19") (pintype "bidirectional"))
    )
    (net (code "74") (name "unconnected-(U2-GPIO3-Pad20)") (class "Default")
      (node (ref "U2") (pin "20") (pinfunction "GPIO3_20") (pintype "bidirectional"))
    )
    (net (code "75") (name "unconnected-(U2-TXRAMP-Pad7)") (class "Default")
      (node (ref "U2") (pin "7") (pinfunction "TXRAMP_7") (pintype "bidirectional"))
    )
    (net (code "76") (name "unconnected-(U2-XOUT-Pad16)") (class "Default")
      (node (ref "U2") (pin "16") (pinfunction "XOUT_16") (pintype "output"))
    )
    (net (code "77") (name "unconnected-(U3-GPIO2-Pad15)") (class "Default")
      (node (ref "U3") (pin "15") (pinfunction "GPIO2_15") (pintype "bidirectional"))
    )
    (net (code "78") (name "unconnected-(U3-GPIO3-Pad11)") (class "Default")
      (node (ref "U3") (pin "11") (pinfunction "GPIO3_11") (pintype "bidirectional"))
    )
    (net (code "79") (name "unconnected-(U3-GPIO4-Pad14)") (class "Default")
      (node (ref "U3") (pin "14") (pinfunction "GPIO4_14") (pintype "bidirectional"))
    )
    (net (code "80") (name "unconnected-(U3-GPIO8-Pad10)") (class "Default")
      (node (ref "U3") (pin "10") (pinfunction "GPIO8_10") (pintype "bidirectional"))
    )
    (net (code "81") (name "unconnected-(U3-NSRESET-Pad30)") (class "Default")
      (node (ref "U3") (pin "30") (pinfunction "NSRESET_30") (pintype "bidirectional"))
    )
    (net (code "82") (name "unconnected-(U3-RTS_SPI-Pad32)") (class "Default")
      (node (ref "U3") (pin "32") (pinfunction "RTS_SPI_32") (pintype "bidirectional"))
    )
    (net (code "83") (name "unconnected-(U3-SYSTEM_ON-Pad2)") (class "Default")
      (node (ref "U3") (pin "2") (pinfunction "SYSTEM_ON_2") (pintype "bidirectional"))
    )
    (net (code "84") (name "unconnected-(U3-XTAL_CLK-Pad22)") (class "Default")
      (node (ref "U3") (pin "22") (pinfunction "XTAL_CLK_22") (pintype "bidirectional"))
    )
    (net (code "85") (name "unconnected-(U5-NC-Pad1)") (class "Default")
      (node (ref "U5") (pin "1") (pinfunction "NC_1") (pintype "no_connect"))
    )
    (net (code "86") (name "unconnected-(U6-NC-Pad1)") (class "Default")
      (node (ref "U6") (pin "1") (pinfunction "NC_1") (pintype "no_connect"))
    )
    (net (code "87") (name "unconnected-(U9-SDO-Pad6)") (class "Default")
      (node (ref "U9") (pin "6") (pinfunction "SDO_6") (pintype "bidirectional"))
    )
    (net (code "88") (name "unconnected-(U12-N.C.-Pad1)") (class "Default")
      (node (ref "U12") (pin "1") (pinfunction "N.C._1") (pintype "no_connect"))
    )
  )
)
